# BAAAHS-BRN01-C.net
KiCad netlist of a schematic drawn in EAGLE
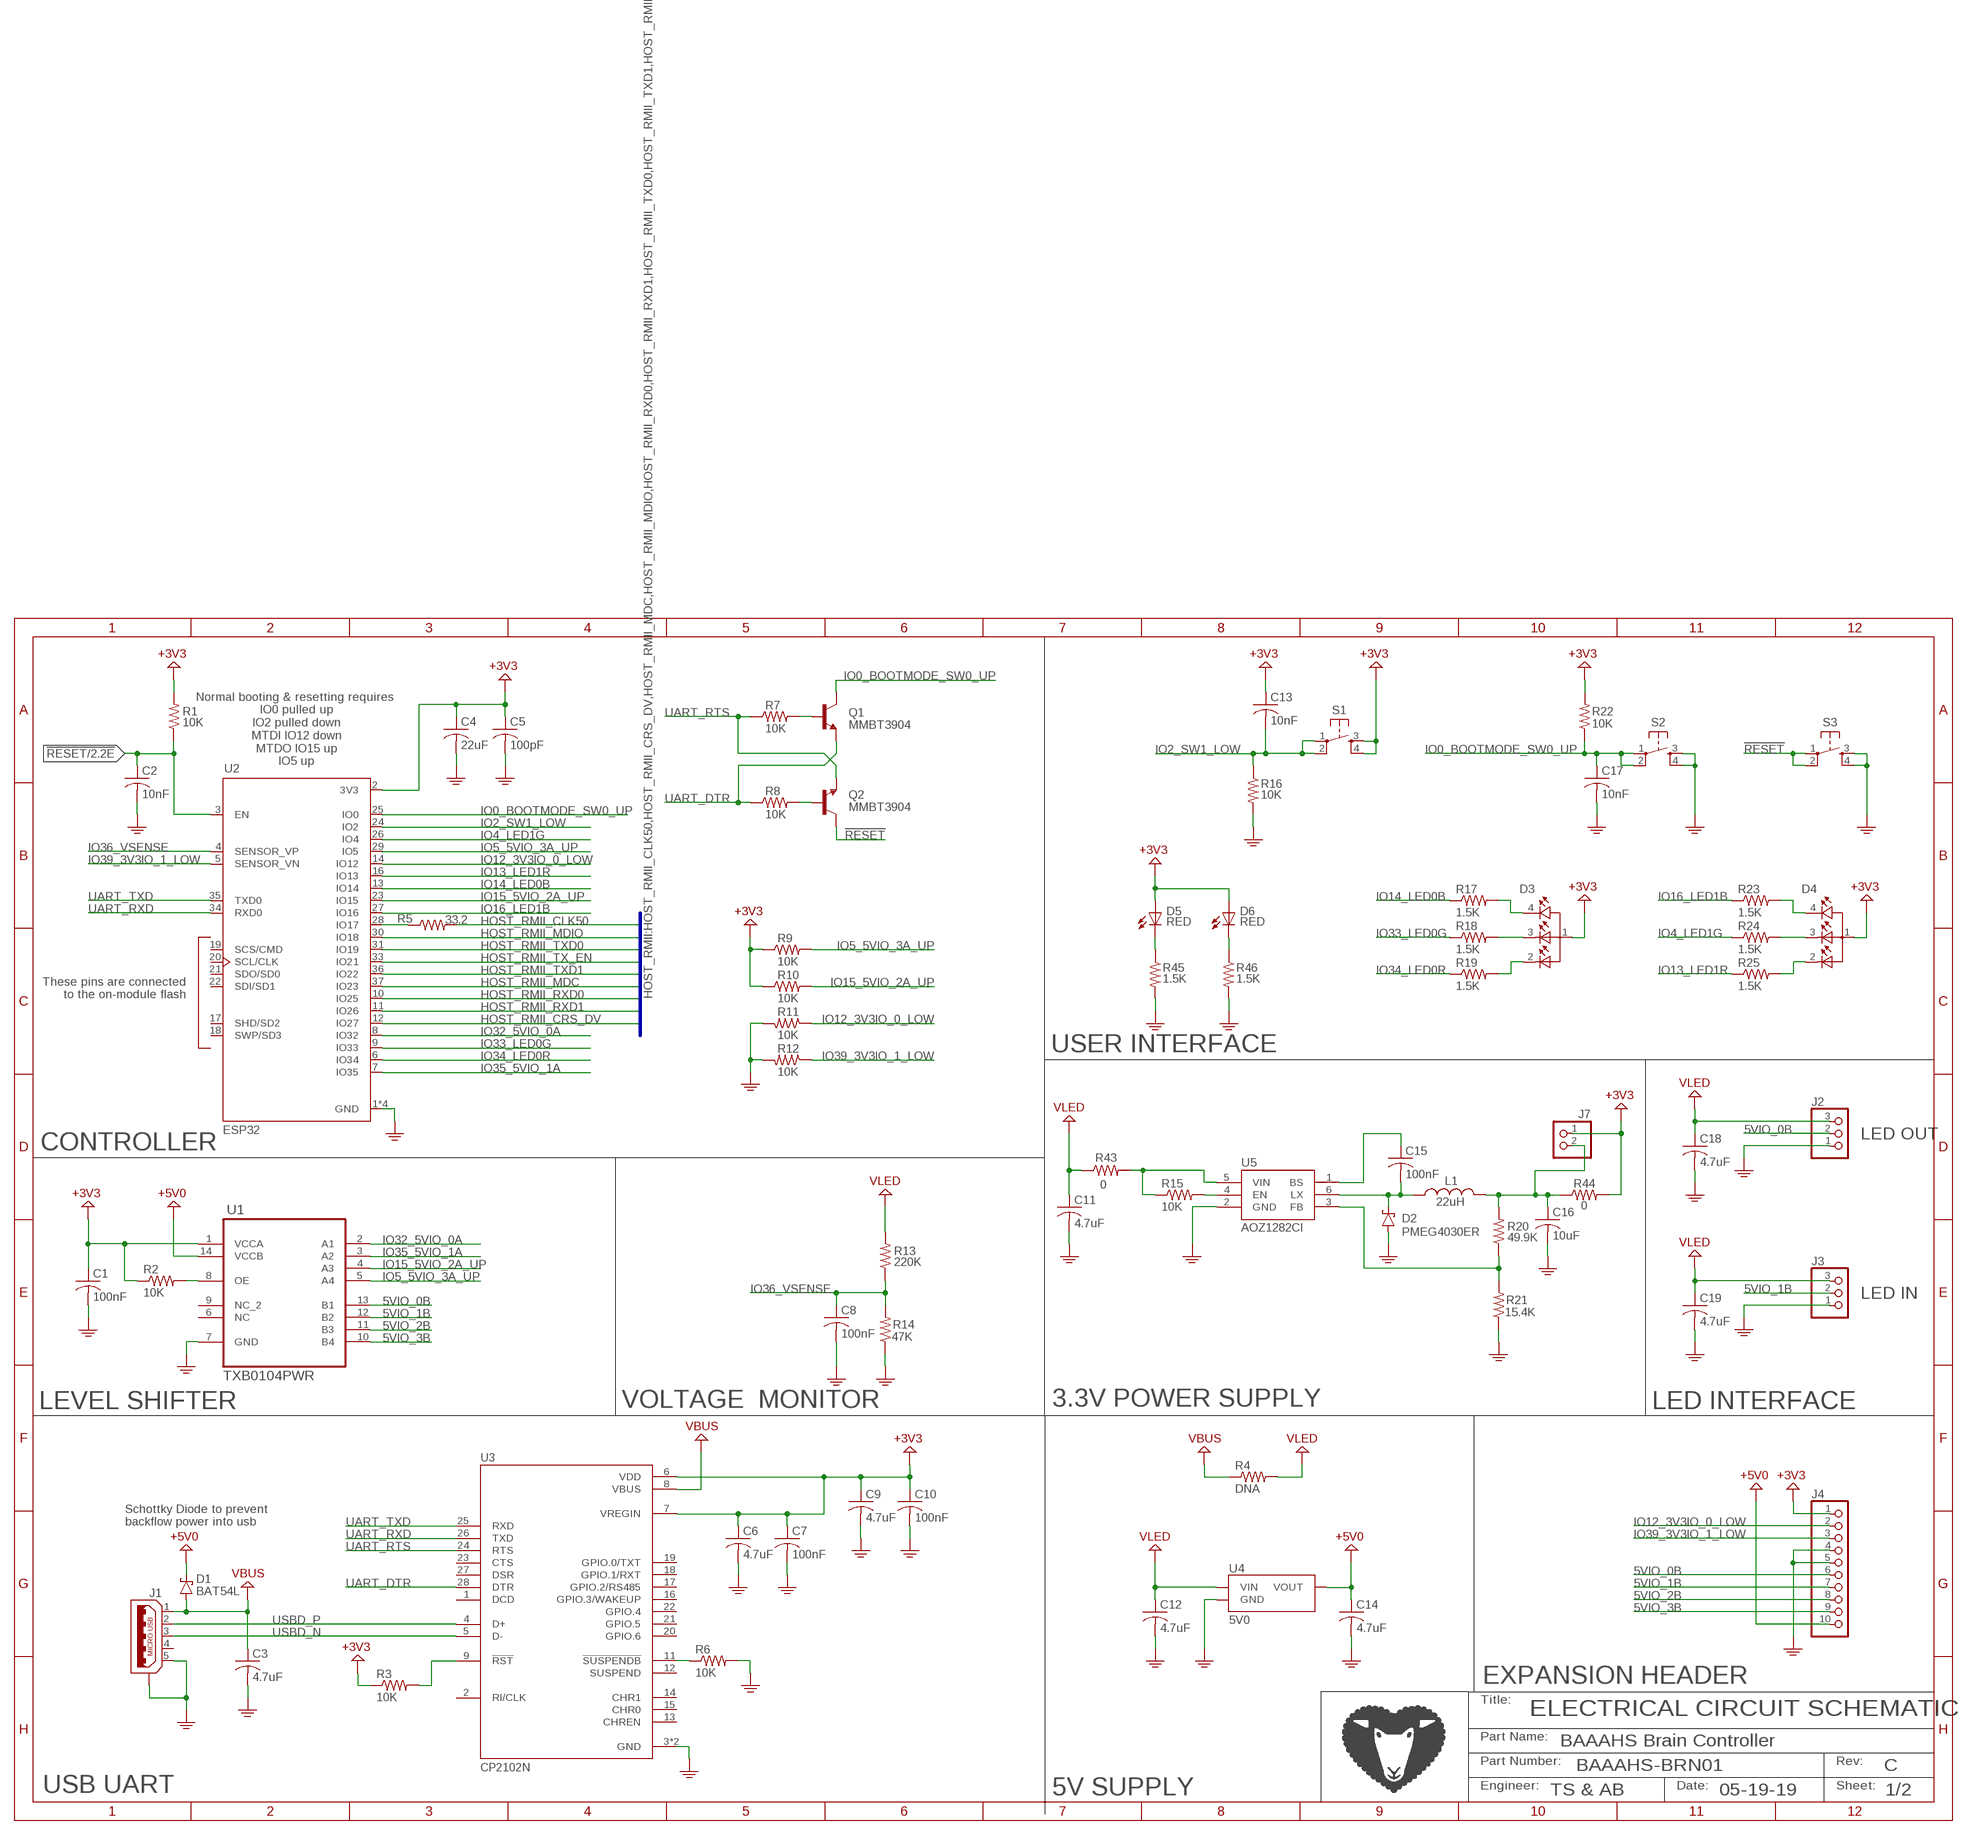
[diagram p0: schematic, sheet 1]
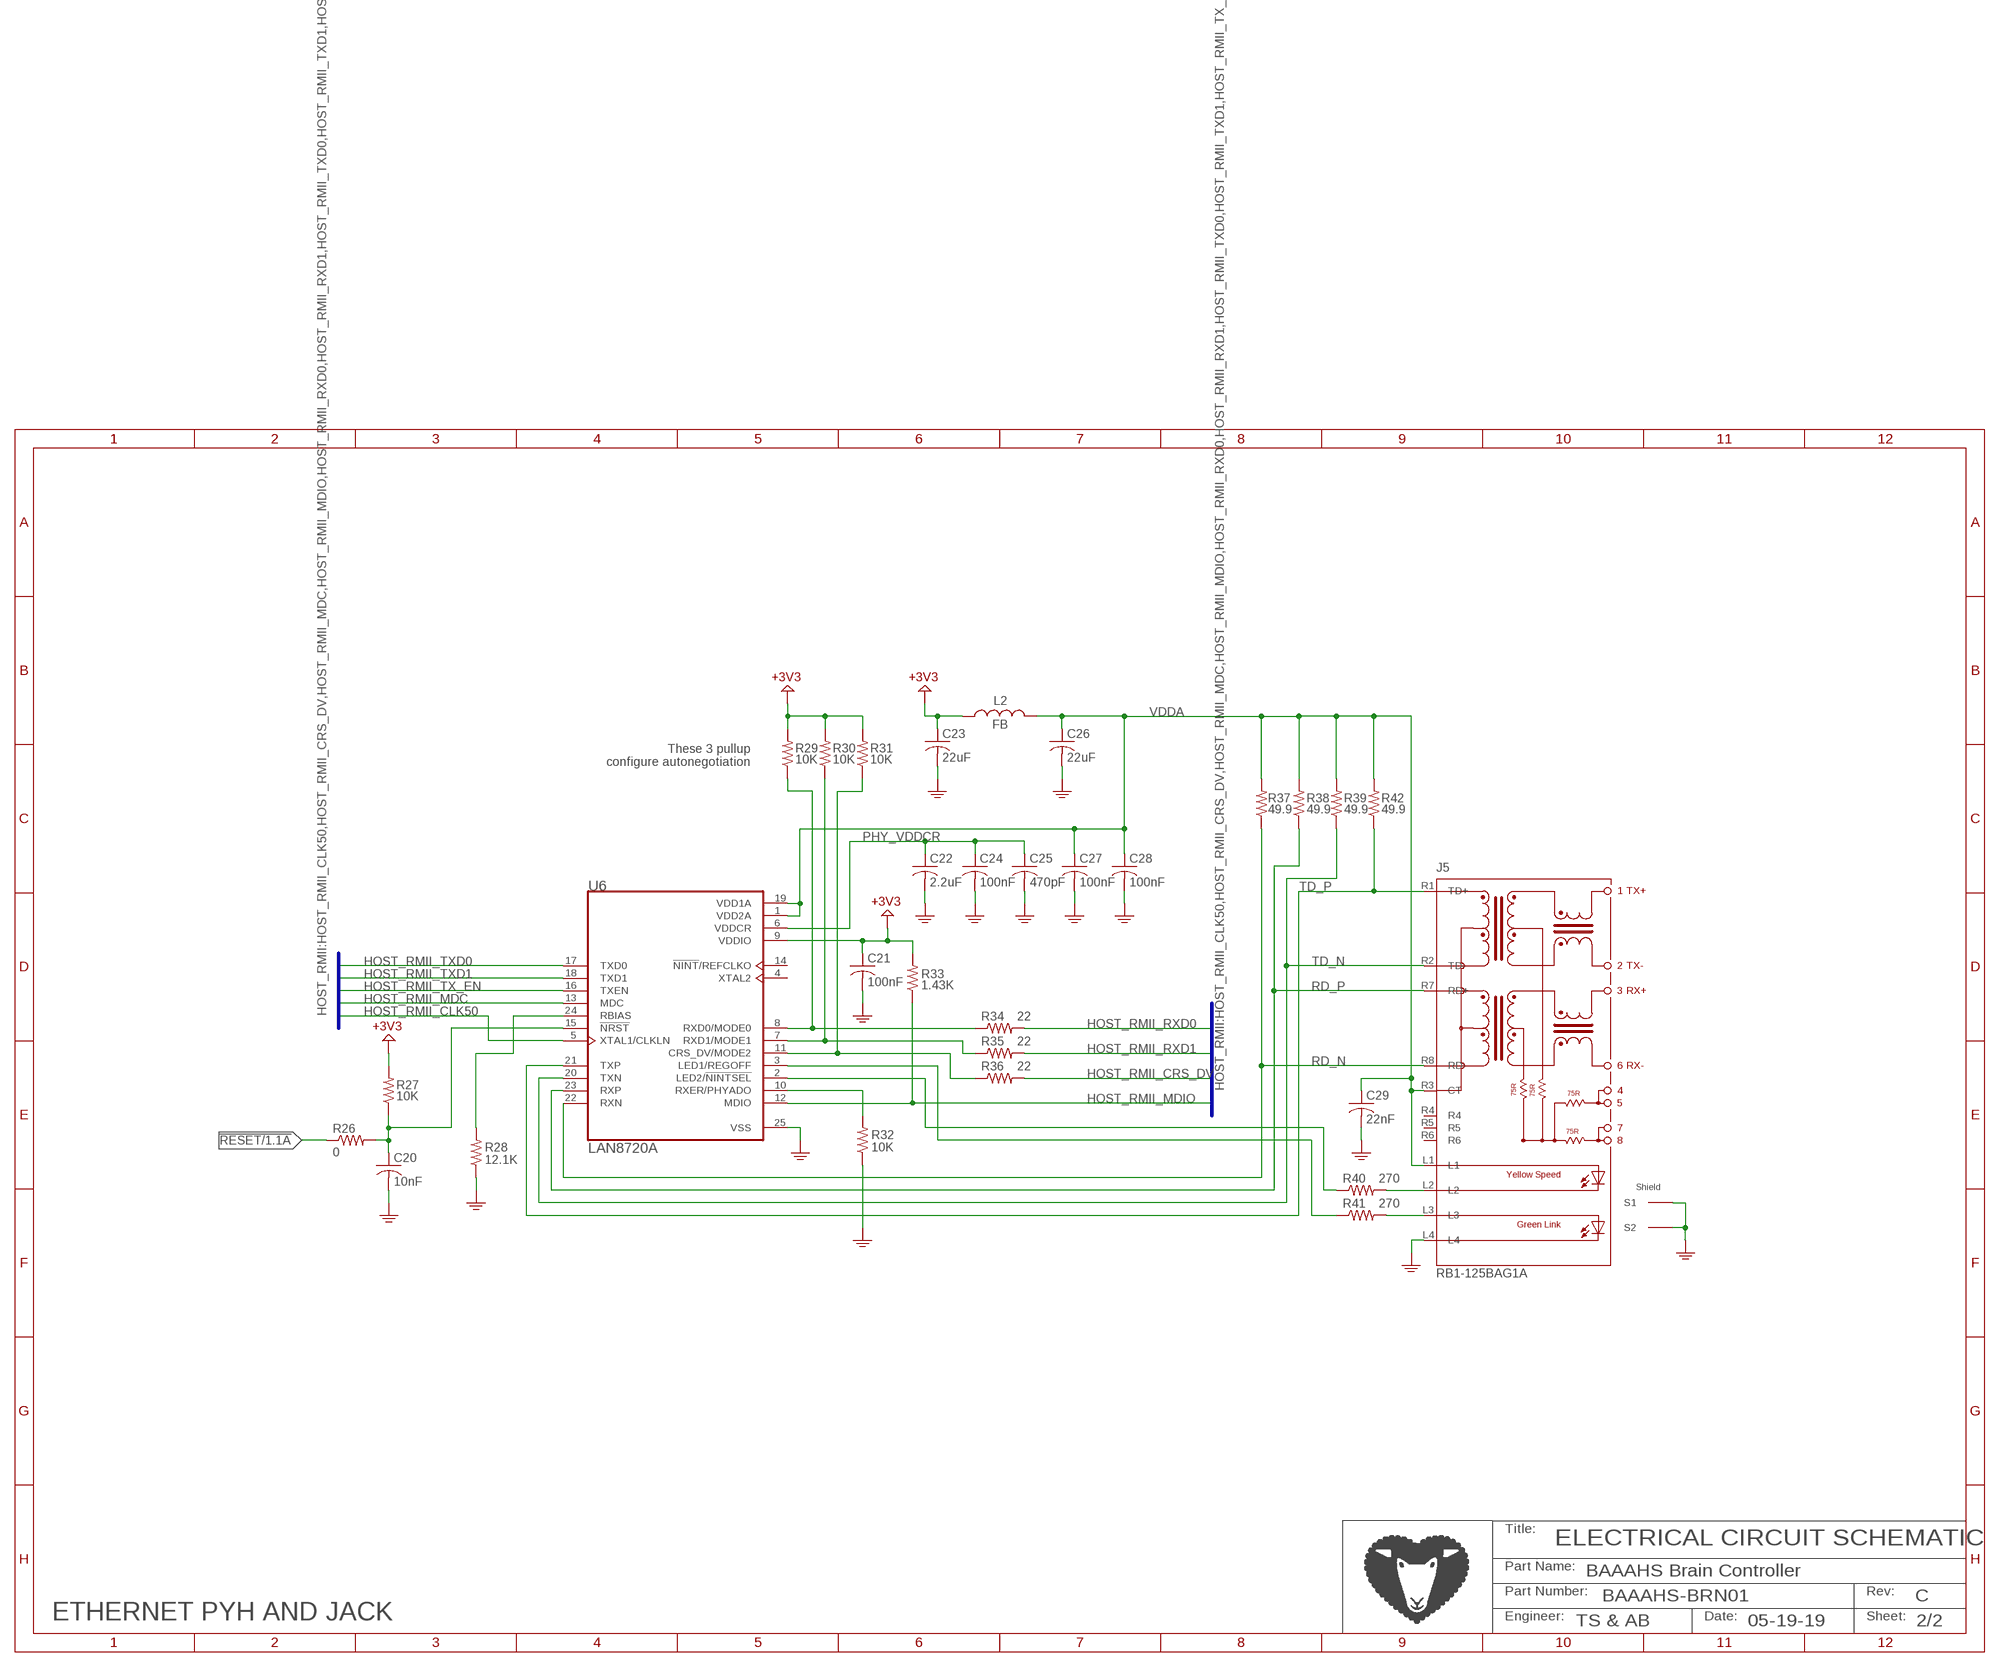
[diagram p1: schematic, sheet 2]

(export (version "E")
  (design (tool "Eeschema 10.0.6"))
  (components
    (comp (ref "C20")
      (value "10nF")
      (footprint "eagle-import:C0402")
      (fields (field (name "TOLERANCE") "+/-10%") (field (name "VOLTAGE") "16V"))
      (libsource (lib "eagle-import") (part "C-C0402-10NF_16V_10%"))
    )
    (comp (ref "C21")
      (value "100nF")
      (footprint "eagle-import:C0402")
      (fields (field (name "TOLERANCE") "+/-10%") (field (name "VOLTAGE") "25V"))
      (libsource (lib "eagle-import") (part "C-C0402-100NF_25V_10%"))
    )
    (comp (ref "C22")
      (value "2.2uF")
      (footprint "eagle-import:C0603")
      (fields (field (name "TOLERANCE") "+/-10%") (field (name "VOLTAGE") "16V"))
      (libsource (lib "eagle-import") (part "C-C0603-2.2UF_16V_10%"))
    )
    (comp (ref "C23")
      (value "22uF")
      (footprint "eagle-import:C0603")
      (fields (field (name "TOLERANCE") "+/-20%") (field (name "VOLTAGE") "10V"))
      (libsource (lib "eagle-import") (part "C-C0603-22UF_10V_20%"))
    )
    (comp (ref "C24")
      (value "100nF")
      (footprint "eagle-import:C0402")
      (fields (field (name "TOLERANCE") "+/-10%") (field (name "VOLTAGE") "25V"))
      (libsource (lib "eagle-import") (part "C-C0402-100NF_25V_10%"))
    )
    (comp (ref "C25")
      (value "470pF")
      (footprint "eagle-import:C0402")
      (fields (field (name "TOLERANCE") "+/-10%") (field (name "VOLTAGE") "50V"))
      (libsource (lib "eagle-import") (part "C-C0402-470PF_50V_10%"))
    )
    (comp (ref "C26")
      (value "22uF")
      (footprint "eagle-import:C0603")
      (fields (field (name "TOLERANCE") "+/-20%") (field (name "VOLTAGE") "10V"))
      (libsource (lib "eagle-import") (part "C-C0603-22UF_10V_20%"))
    )
    (comp (ref "C27")
      (value "100nF")
      (footprint "eagle-import:C0402")
      (fields (field (name "TOLERANCE") "+/-10%") (field (name "VOLTAGE") "25V"))
      (libsource (lib "eagle-import") (part "C-C0402-100NF_25V_10%"))
    )
    (comp (ref "C28")
      (value "100nF")
      (footprint "eagle-import:C0402")
      (fields (field (name "TOLERANCE") "+/-10%") (field (name "VOLTAGE") "25V"))
      (libsource (lib "eagle-import") (part "C-C0402-100NF_25V_10%"))
    )
    (comp (ref "C29")
      (value "22nF")
      (footprint "eagle-import:C0402")
      (fields (field (name "TOLERANCE") "+/-10%") (field (name "VOLTAGE") "16V"))
      (libsource (lib "eagle-import") (part "C-C0402-22NF_16V_10%"))
    )
    (comp (ref "J5")
      (value "RB1-125BAG1A")
      (footprint "eagle-import:WIZNET_RB1-125BAG1A")
      (libsource (lib "eagle-import") (part "RB1-125BAG1A"))
    )
    (comp (ref "L2")
      (value "FB")
      (footprint "eagle-import:L0603")
      (libsource (lib "eagle-import") (part "FB-L0603-600OHM_0.2A"))
    )
    (comp (ref "R26")
      (value "0")
      (footprint "eagle-import:R0402")
      (fields (field (name "POWER") "1/16W") (field (name "TOLERANCE") "1%"))
      (libsource (lib "eagle-import") (part "R-R0402-0_1%"))
    )
    (comp (ref "R27")
      (value "10K")
      (footprint "eagle-import:R0402")
      (fields (field (name "POWER") "1/16W") (field (name "TOLERANCE") "1%"))
      (libsource (lib "eagle-import") (part "R-R0402-10K_1%"))
    )
    (comp (ref "R28")
      (value "12.1K")
      (footprint "eagle-import:R0402")
      (fields (field (name "POWER") "1/16W") (field (name "TOLERANCE") "1%"))
      (libsource (lib "eagle-import") (part "R-R0402-12.1K_1%"))
    )
    (comp (ref "R29")
      (value "10K")
      (footprint "eagle-import:R0402")
      (fields (field (name "POWER") "1/16W") (field (name "TOLERANCE") "1%"))
      (libsource (lib "eagle-import") (part "R-R0402-10K_1%"))
    )
    (comp (ref "R30")
      (value "10K")
      (footprint "eagle-import:R0402")
      (fields (field (name "POWER") "1/16W") (field (name "TOLERANCE") "1%"))
      (libsource (lib "eagle-import") (part "R-R0402-10K_1%"))
    )
    (comp (ref "R31")
      (value "10K")
      (footprint "eagle-import:R0402")
      (fields (field (name "POWER") "1/16W") (field (name "TOLERANCE") "1%"))
      (libsource (lib "eagle-import") (part "R-R0402-10K_1%"))
    )
    (comp (ref "R32")
      (value "10K")
      (footprint "eagle-import:R0402")
      (fields (field (name "POWER") "1/16W") (field (name "TOLERANCE") "1%"))
      (libsource (lib "eagle-import") (part "R-R0402-10K_1%"))
    )
    (comp (ref "R33")
      (value "1.43K")
      (footprint "eagle-import:R0402")
      (fields (field (name "POWER") "1/16W") (field (name "TOLERANCE") "1%"))
      (libsource (lib "eagle-import") (part "R-R0402-1.43K_1%"))
    )
    (comp (ref "R34")
      (value "22")
      (footprint "eagle-import:R0402")
      (fields (field (name "POWER") "1/16W") (field (name "TOLERANCE") "1%"))
      (libsource (lib "eagle-import") (part "R-R0402-22_1%"))
    )
    (comp (ref "R35")
      (value "22")
      (footprint "eagle-import:R0402")
      (fields (field (name "POWER") "1/16W") (field (name "TOLERANCE") "1%"))
      (libsource (lib "eagle-import") (part "R-R0402-22_1%"))
    )
    (comp (ref "R36")
      (value "22")
      (footprint "eagle-import:R0402")
      (fields (field (name "POWER") "1/16W") (field (name "TOLERANCE") "1%"))
      (libsource (lib "eagle-import") (part "R-R0402-22_1%"))
    )
    (comp (ref "R37")
      (value "49.9")
      (footprint "eagle-import:R0402")
      (fields (field (name "POWER") "1/16W") (field (name "TOLERANCE") "1%"))
      (libsource (lib "eagle-import") (part "R-R0402-49.9_1%"))
    )
    (comp (ref "R38")
      (value "49.9")
      (footprint "eagle-import:R0402")
      (fields (field (name "POWER") "1/16W") (field (name "TOLERANCE") "1%"))
      (libsource (lib "eagle-import") (part "R-R0402-49.9_1%"))
    )
    (comp (ref "R39")
      (value "49.9")
      (footprint "eagle-import:R0402")
      (fields (field (name "POWER") "1/16W") (field (name "TOLERANCE") "1%"))
      (libsource (lib "eagle-import") (part "R-R0402-49.9_1%"))
    )
    (comp (ref "R40")
      (value "270")
      (footprint "eagle-import:R0402")
      (fields (field (name "POWER") "1/16W") (field (name "TOLERANCE") "1%"))
      (libsource (lib "eagle-import") (part "R-R0402-270_1%"))
    )
    (comp (ref "R41")
      (value "270")
      (footprint "eagle-import:R0402")
      (fields (field (name "POWER") "1/16W") (field (name "TOLERANCE") "1%"))
      (libsource (lib "eagle-import") (part "R-R0402-270_1%"))
    )
    (comp (ref "R42")
      (value "49.9")
      (footprint "eagle-import:R0402")
      (fields (field (name "POWER") "1/16W") (field (name "TOLERANCE") "1%"))
      (libsource (lib "eagle-import") (part "R-R0402-49.9_1%"))
    )
    (comp (ref "U6")
      (value "LAN8720A")
      (footprint "eagle-import:QFN50P400X400X100-25N")
      (libsource (lib "eagle-import") (part "LAN8720A-CP"))
    )
    (comp (ref "C1")
      (value "100nF")
      (footprint "eagle-import:C0402")
      (fields (field (name "TOLERANCE") "+/-10%") (field (name "VOLTAGE") "25V"))
      (libsource (lib "eagle-import") (part "C-C0402-100NF_25V_10%"))
    )
    (comp (ref "C2")
      (value "10nF")
      (footprint "eagle-import:C0402")
      (fields (field (name "TOLERANCE") "+/-10%") (field (name "VOLTAGE") "16V"))
      (libsource (lib "eagle-import") (part "C-C0402-10NF_16V_10%"))
    )
    (comp (ref "C3")
      (value "4.7uF")
      (footprint "eagle-import:C0402")
      (fields (field (name "TOLERANCE") "+/-10%") (field (name "VOLTAGE") "10V"))
      (libsource (lib "eagle-import") (part "C-C0402-4.7UF_10V_10%"))
    )
    (comp (ref "C4")
      (value "22uF")
      (footprint "eagle-import:C0603")
      (fields (field (name "TOLERANCE") "+/-20%") (field (name "VOLTAGE") "10V"))
      (libsource (lib "eagle-import") (part "C-C0603-22UF_10V_20%"))
    )
    (comp (ref "C5")
      (value "100pF")
      (footprint "eagle-import:C0402")
      (fields (field (name "TOLERANCE") "+/-5%") (field (name "VOLTAGE") "50V"))
      (libsource (lib "eagle-import") (part "C-C0402-100PF_50V_5%"))
    )
    (comp (ref "C6")
      (value "4.7uF")
      (footprint "eagle-import:C0402")
      (fields (field (name "TOLERANCE") "+/-10%") (field (name "VOLTAGE") "10V"))
      (libsource (lib "eagle-import") (part "C-C0402-4.7UF_10V_10%"))
    )
    (comp (ref "C7")
      (value "100nF")
      (footprint "eagle-import:C0402")
      (fields (field (name "TOLERANCE") "+/-10%") (field (name "VOLTAGE") "25V"))
      (libsource (lib "eagle-import") (part "C-C0402-100NF_25V_10%"))
    )
    (comp (ref "C8")
      (value "100nF")
      (footprint "eagle-import:C0402")
      (fields (field (name "TOLERANCE") "+/-10%") (field (name "VOLTAGE") "25V"))
      (libsource (lib "eagle-import") (part "C-C0402-100NF_25V_10%"))
    )
    (comp (ref "C9")
      (value "4.7uF")
      (footprint "eagle-import:C0402")
      (fields (field (name "TOLERANCE") "+/-10%") (field (name "VOLTAGE") "10V"))
      (libsource (lib "eagle-import") (part "C-C0402-4.7UF_10V_10%"))
    )
    (comp (ref "C10")
      (value "100nF")
      (footprint "eagle-import:C0402")
      (fields (field (name "TOLERANCE") "+/-10%") (field (name "VOLTAGE") "25V"))
      (libsource (lib "eagle-import") (part "C-C0402-100NF_25V_10%"))
    )
    (comp (ref "C11")
      (value "4.7uF")
      (footprint "eagle-import:C0603")
      (fields (field (name "TOLERANCE") "+/-10%") (field (name "VOLTAGE") "25V"))
      (libsource (lib "eagle-import") (part "C-C0603-4.7UF_25V_10%"))
    )
    (comp (ref "C12")
      (value "4.7uF")
      (footprint "eagle-import:C0603")
      (fields (field (name "TOLERANCE") "+/-10%") (field (name "VOLTAGE") "25V"))
      (libsource (lib "eagle-import") (part "C-C0603-4.7UF_25V_10%"))
    )
    (comp (ref "C13")
      (value "10nF")
      (footprint "eagle-import:C0402")
      (fields (field (name "TOLERANCE") "+/-10%") (field (name "VOLTAGE") "16V"))
      (libsource (lib "eagle-import") (part "C-C0402-10NF_16V_10%"))
    )
    (comp (ref "C14")
      (value "4.7uF")
      (footprint "eagle-import:C0402")
      (fields (field (name "TOLERANCE") "+/-10%") (field (name "VOLTAGE") "10V"))
      (libsource (lib "eagle-import") (part "C-C0402-4.7UF_10V_10%"))
    )
    (comp (ref "C15")
      (value "100nF")
      (footprint "eagle-import:C0402")
      (fields (field (name "TOLERANCE") "+/-10%") (field (name "VOLTAGE") "25V"))
      (libsource (lib "eagle-import") (part "C-C0402-100NF_25V_10%"))
    )
    (comp (ref "C16")
      (value "10uF")
      (footprint "eagle-import:C0603")
      (fields (field (name "TOLERANCE") "+/-20%") (field (name "VOLTAGE") "25V"))
      (libsource (lib "eagle-import") (part "C-C0603-10UF_25V_20%"))
    )
    (comp (ref "C17")
      (value "10nF")
      (footprint "eagle-import:C0402")
      (fields (field (name "TOLERANCE") "+/-10%") (field (name "VOLTAGE") "16V"))
      (libsource (lib "eagle-import") (part "C-C0402-10NF_16V_10%"))
    )
    (comp (ref "C18")
      (value "4.7uF")
      (footprint "eagle-import:C0603")
      (fields (field (name "TOLERANCE") "+/-10%") (field (name "VOLTAGE") "25V"))
      (libsource (lib "eagle-import") (part "C-C0603-4.7UF_25V_10%"))
    )
    (comp (ref "C19")
      (value "4.7uF")
      (footprint "eagle-import:C0603")
      (fields (field (name "TOLERANCE") "+/-10%") (field (name "VOLTAGE") "25V"))
      (libsource (lib "eagle-import") (part "C-C0603-4.7UF_25V_10%"))
    )
    (comp (ref "D1")
      (value "BAT54L")
      (footprint "eagle-import:SOT23")
      (libsource (lib "eagle-import") (part "D_SCHOTTKY-SOT23"))
    )
    (comp (ref "D2")
      (value "PMEG4030ER")
      (footprint "eagle-import:SOD123")
      (libsource (lib "eagle-import") (part "D_SCHOTTKY-SOD123-PMEG4030ER_40V"))
    )
    (comp (ref "D3")
      (value "APTF1616LSEEZGKQBKC")
      (footprint "eagle-import:LEDSC160X160X070-4N")
      (libsource (lib "eagle-import") (part "APTF1616LSEEZGKQBKC"))
    )
    (comp (ref "D4")
      (value "APTF1616LSEEZGKQBKC")
      (footprint "eagle-import:LEDSC160X160X070-4N")
      (libsource (lib "eagle-import") (part "APTF1616LSEEZGKQBKC"))
    )
    (comp (ref "D5")
      (value "RED")
      (footprint "eagle-import:D0603")
      (libsource (lib "eagle-import") (part "LED-D0603-RED_54MCD"))
    )
    (comp (ref "D6")
      (value "RED")
      (footprint "eagle-import:D0603")
      (libsource (lib "eagle-import") (part "LED-D0603-RED_54MCD"))
    )
    (comp (ref "J1")
      (value "USB_MICRO-FCI-USB_MICRO_A_RA")
      (footprint "eagle-import:USB_MICRO_A_RA")
      (libsource (lib "eagle-import") (part "USB_MICRO-USB_MICRO_A_RA-FCI"))
    )
    (comp (ref "J2")
      (value "PINHD1X3-20AWG")
      (footprint "eagle-import:3WAY_LED_WIRES")
      (libsource (lib "eagle-import") (part "PINHD1X3-20AWG"))
    )
    (comp (ref "J3")
      (value "PINHD1X3-20AWG")
      (footprint "eagle-import:3WAY_LED_WIRES")
      (libsource (lib "eagle-import") (part "PINHD1X3-20AWG"))
    )
    (comp (ref "J4")
      (value "PINHD1X10-1X10")
      (footprint "eagle-import:1X10")
      (libsource (lib "eagle-import") (part "PINHD1X10-1X10"))
    )
    (comp (ref "J7")
      (value "PINHD1X2-1X02")
      (footprint "eagle-import:1X02")
      (libsource (lib "eagle-import") (part "PINHD1X2-1X02"))
    )
    (comp (ref "L1")
      (value "22uH")
      (footprint "eagle-import:NRG4026")
      (libsource (lib "eagle-import") (part "L-NRG4026-22UH__290MOHM_700MA"))
    )
    (comp (ref "Q1")
      (value "MMBT3904")
      (footprint "eagle-import:SOT23")
      (fields (field (name "VOLTAGE") "40V"))
      (libsource (lib "eagle-import") (part "NPN-SOT23-MMBT3904_40V"))
    )
    (comp (ref "Q2")
      (value "MMBT3904")
      (footprint "eagle-import:SOT23")
      (fields (field (name "VOLTAGE") "40V"))
      (libsource (lib "eagle-import") (part "NPN-SOT23-MMBT3904_40V"))
    )
    (comp (ref "R1")
      (value "10K")
      (footprint "eagle-import:R0402")
      (fields (field (name "POWER") "1/16W") (field (name "TOLERANCE") "1%"))
      (libsource (lib "eagle-import") (part "R-R0402-10K_1%"))
    )
    (comp (ref "R2")
      (value "10K")
      (footprint "eagle-import:R0402")
      (fields (field (name "POWER") "1/16W") (field (name "TOLERANCE") "1%"))
      (libsource (lib "eagle-import") (part "R-R0402-10K_1%"))
    )
    (comp (ref "R3")
      (value "10K")
      (footprint "eagle-import:R0402")
      (fields (field (name "POWER") "1/16W") (field (name "TOLERANCE") "1%"))
      (libsource (lib "eagle-import") (part "R-R0402-10K_1%"))
    )
    (comp (ref "R4")
      (value "DNA")
      (footprint "eagle-import:R0603")
      (fields (field (name "POWER") "1/16W"))
      (libsource (lib "eagle-import") (part "R-R0603-DNA"))
    )
    (comp (ref "R5")
      (value "33.2")
      (footprint "eagle-import:R0402")
      (fields (field (name "POWER") "1/16W") (field (name "TOLERANCE") "1%"))
      (libsource (lib "eagle-import") (part "R-R0402-33.2_1%"))
    )
    (comp (ref "R6")
      (value "10K")
      (footprint "eagle-import:R0402")
      (fields (field (name "POWER") "1/16W") (field (name "TOLERANCE") "1%"))
      (libsource (lib "eagle-import") (part "R-R0402-10K_1%"))
    )
    (comp (ref "R7")
      (value "10K")
      (footprint "eagle-import:R0402")
      (fields (field (name "POWER") "1/16W") (field (name "TOLERANCE") "1%"))
      (libsource (lib "eagle-import") (part "R-R0402-10K_1%"))
    )
    (comp (ref "R8")
      (value "10K")
      (footprint "eagle-import:R0402")
      (fields (field (name "POWER") "1/16W") (field (name "TOLERANCE") "1%"))
      (libsource (lib "eagle-import") (part "R-R0402-10K_1%"))
    )
    (comp (ref "R9")
      (value "10K")
      (footprint "eagle-import:R0402")
      (fields (field (name "POWER") "1/16W") (field (name "TOLERANCE") "1%"))
      (libsource (lib "eagle-import") (part "R-R0402-10K_1%"))
    )
    (comp (ref "R10")
      (value "10K")
      (footprint "eagle-import:R0402")
      (fields (field (name "POWER") "1/16W") (field (name "TOLERANCE") "1%"))
      (libsource (lib "eagle-import") (part "R-R0402-10K_1%"))
    )
    (comp (ref "R11")
      (value "10K")
      (footprint "eagle-import:R0402")
      (fields (field (name "POWER") "1/16W") (field (name "TOLERANCE") "1%"))
      (libsource (lib "eagle-import") (part "R-R0402-10K_1%"))
    )
    (comp (ref "R12")
      (value "10K")
      (footprint "eagle-import:R0402")
      (fields (field (name "POWER") "1/16W") (field (name "TOLERANCE") "1%"))
      (libsource (lib "eagle-import") (part "R-R0402-10K_1%"))
    )
    (comp (ref "R13")
      (value "220K")
      (footprint "eagle-import:R0402")
      (fields (field (name "POWER") "1/16W") (field (name "TOLERANCE") "1%"))
      (libsource (lib "eagle-import") (part "R-R0402-220K_1%"))
    )
    (comp (ref "R14")
      (value "47K")
      (footprint "eagle-import:R0402")
      (fields (field (name "POWER") "1/16W") (field (name "TOLERANCE") "1%"))
      (libsource (lib "eagle-import") (part "R-R0402-47K_1%"))
    )
    (comp (ref "R15")
      (value "10K")
      (footprint "eagle-import:R0402")
      (fields (field (name "POWER") "1/16W") (field (name "TOLERANCE") "1%"))
      (libsource (lib "eagle-import") (part "R-R0402-10K_1%"))
    )
    (comp (ref "R16")
      (value "10K")
      (footprint "eagle-import:R0402")
      (fields (field (name "POWER") "1/16W") (field (name "TOLERANCE") "1%"))
      (libsource (lib "eagle-import") (part "R-R0402-10K_1%"))
    )
    (comp (ref "R17")
      (value "1.5K")
      (footprint "eagle-import:R0402")
      (fields (field (name "POWER") "1/16W") (field (name "TOLERANCE") "1%"))
      (libsource (lib "eagle-import") (part "R-R0402-1.5K_1%"))
    )
    (comp (ref "R18")
      (value "1.5K")
      (footprint "eagle-import:R0402")
      (fields (field (name "POWER") "1/16W") (field (name "TOLERANCE") "1%"))
      (libsource (lib "eagle-import") (part "R-R0402-1.5K_1%"))
    )
    (comp (ref "R19")
      (value "1.5K")
      (footprint "eagle-import:R0402")
      (fields (field (name "POWER") "1/16W") (field (name "TOLERANCE") "1%"))
      (libsource (lib "eagle-import") (part "R-R0402-1.5K_1%"))
    )
    (comp (ref "R20")
      (value "49.9K")
      (footprint "eagle-import:R0402")
      (fields (field (name "POWER") "1/16W") (field (name "TOLERANCE") "1%"))
      (libsource (lib "eagle-import") (part "R-R0402-49.9K_1%"))
    )
    (comp (ref "R21")
      (value "15.4K")
      (footprint "eagle-import:R0402")
      (fields (field (name "POWER") "1/16W") (field (name "TOLERANCE") "1%"))
      (libsource (lib "eagle-import") (part "R-R0402-15.4K_1%"))
    )
    (comp (ref "R22")
      (value "10K")
      (footprint "eagle-import:R0402")
      (fields (field (name "POWER") "1/16W") (field (name "TOLERANCE") "1%"))
      (libsource (lib "eagle-import") (part "R-R0402-10K_1%"))
    )
    (comp (ref "R23")
      (value "1.5K")
      (footprint "eagle-import:R0402")
      (fields (field (name "POWER") "1/16W") (field (name "TOLERANCE") "1%"))
      (libsource (lib "eagle-import") (part "R-R0402-1.5K_1%"))
    )
    (comp (ref "R24")
      (value "1.5K")
      (footprint "eagle-import:R0402")
      (fields (field (name "POWER") "1/16W") (field (name "TOLERANCE") "1%"))
      (libsource (lib "eagle-import") (part "R-R0402-1.5K_1%"))
    )
    (comp (ref "R25")
      (value "1.5K")
      (footprint "eagle-import:R0402")
      (fields (field (name "POWER") "1/16W") (field (name "TOLERANCE") "1%"))
      (libsource (lib "eagle-import") (part "R-R0402-1.5K_1%"))
    )
    (comp (ref "R43")
      (value "0")
      (footprint "eagle-import:R0603")
      (fields (field (name "POWER") "1/10W") (field (name "TOLERANCE") "1%"))
      (libsource (lib "eagle-import") (part "R-R0603-0_1%"))
    )
    (comp (ref "R44")
      (value "0")
      (footprint "eagle-import:R0603")
      (fields (field (name "POWER") "1/10W") (field (name "TOLERANCE") "1%"))
      (libsource (lib "eagle-import") (part "R-R0603-0_1%"))
    )
    (comp (ref "R45")
      (value "1.5K")
      (footprint "eagle-import:R0402")
      (fields (field (name "POWER") "1/16W") (field (name "TOLERANCE") "1%"))
      (libsource (lib "eagle-import") (part "R-R0402-1.5K_1%"))
    )
    (comp (ref "R46")
      (value "1.5K")
      (footprint "eagle-import:R0402")
      (fields (field (name "POWER") "1/16W") (field (name "TOLERANCE") "1%"))
      (libsource (lib "eagle-import") (part "R-R0402-1.5K_1%"))
    )
    (comp (ref "S1")
      (value "SW4-SM6MM")
      (footprint "eagle-import:SM6MM")
      (libsource (lib "eagle-import") (part "SW4-SM6MM"))
    )
    (comp (ref "S2")
      (value "SW4-SM6MM")
      (footprint "eagle-import:SM6MM")
      (libsource (lib "eagle-import") (part "SW4-SM6MM"))
    )
    (comp (ref "S3")
      (value "SW4-SM6MM")
      (footprint "eagle-import:SM6MM")
      (libsource (lib "eagle-import") (part "SW4-SM6MM"))
    )
    (comp (ref "U1")
      (value "TXB0104PWR")
      (footprint "eagle-import:SOP65P640X120-14N")
      (libsource (lib "eagle-import") (part "TXB0104PWR"))
    )
    (comp (ref "U2")
      (value "ESP32")
      (footprint "eagle-import:MODULE_ESP32WROOM32D")
      (libsource (lib "eagle-import") (part "ESP32WROOM32D-MODULE_ESP32WROOM32D"))
    )
    (comp (ref "U3")
      (value "CP2102N")
      (footprint "eagle-import:QFN50P500X500X80_29N")
      (libsource (lib "eagle-import") (part "CP2102N-A01-GQFN28"))
    )
    (comp (ref "U4")
      (value "5V0")
      (footprint "eagle-import:SOT23")
      (libsource (lib "eagle-import") (part "TLV76050DBZR-SOT23"))
    )
    (comp (ref "U5")
      (value "AOZ1282CI")
      (footprint "eagle-import:SOT23_6")
      (libsource (lib "eagle-import") (part "AOZ1282CI-SOT23_6"))
    )
  )
  (nets
    (net (code "5") (name "3V3") (class "Default")
      (node (ref "C1") (pin "1") (pinfunction "1_1") (pintype "passive"))
      (node (ref "C10") (pin "1") (pinfunction "1_1") (pintype "passive"))
      (node (ref "C13") (pin "1") (pinfunction "1_1") (pintype "passive"))
      (node (ref "C21") (pin "1") (pinfunction "1_1") (pintype "passive"))
      (node (ref "C23") (pin "1") (pinfunction "1_1") (pintype "passive"))
      (node (ref "C4") (pin "1") (pinfunction "1_1") (pintype "passive"))
      (node (ref "C5") (pin "1") (pinfunction "1_1") (pintype "passive"))
      (node (ref "C6") (pin "1") (pinfunction "1_1") (pintype "passive"))
      (node (ref "C7") (pin "1") (pinfunction "1_1") (pintype "passive"))
      (node (ref "C9") (pin "1") (pinfunction "1_1") (pintype "passive"))
      (node (ref "D3") (pin "1") (pinfunction "1_1") (pintype "passive"))
      (node (ref "D4") (pin "1") (pinfunction "1_1") (pintype "passive"))
      (node (ref "D5") (pin "A") (pinfunction "A_A") (pintype "passive"))
      (node (ref "D6") (pin "A") (pinfunction "A_A") (pintype "passive"))
      (node (ref "J4") (pin "1") (pinfunction "1_1") (pintype "passive"))
      (node (ref "J7") (pin "1") (pinfunction "1_1") (pintype "passive"))
      (node (ref "L2") (pin "1") (pinfunction "1_1") (pintype "passive"))
      (node (ref "R1") (pin "2") (pinfunction "2_2") (pintype "passive"))
      (node (ref "R10") (pin "1") (pinfunction "1_1") (pintype "passive"))
      (node (ref "R2") (pin "1") (pinfunction "1_1") (pintype "passive"))
      (node (ref "R22") (pin "2") (pinfunction "2_2") (pintype "passive"))
      (node (ref "R27") (pin "2") (pinfunction "2_2") (pintype "passive"))
      (node (ref "R29") (pin "2") (pinfunction "2_2") (pintype "passive"))
      (node (ref "R3") (pin "1") (pinfunction "1_1") (pintype "passive"))
      (node (ref "R30") (pin "2") (pinfunction "2_2") (pintype "passive"))
      (node (ref "R31") (pin "2") (pinfunction "2_2") (pintype "passive"))
      (node (ref "R33") (pin "2") (pinfunction "2_2") (pintype "passive"))
      (node (ref "R44") (pin "2") (pinfunction "2_2") (pintype "passive"))
      (node (ref "R9") (pin "1") (pinfunction "1_1") (pintype "passive"))
      (node (ref "S1") (pin "3") (pinfunction "S_3") (pintype "passive"))
      (node (ref "S1") (pin "4") (pinfunction "S1_4") (pintype "passive"))
      (node (ref "U1") (pin "1") (pinfunction "VCCA_1") (pintype "power_in"))
      (node (ref "U2") (pin "2") (pinfunction "3V3_2") (pintype "power_in"))
      (node (ref "U3") (pin "6") (pinfunction "VDD_6") (pintype "power_in"))
      (node (ref "U3") (pin "7") (pinfunction "VREGIN_7") (pintype "power_in"))
      (node (ref "U6") (pin "9") (pinfunction "VDDIO_9") (pintype "power_in"))
    )
    (net (code "6") (name "5V0") (class "Default")
      (node (ref "C14") (pin "1") (pinfunction "1_1") (pintype "passive"))
      (node (ref "D1") (pin "3") (pinfunction "C_3") (pintype "passive"))
      (node (ref "J4") (pin "10") (pinfunction "10_10") (pintype "passive"))
      (node (ref "U1") (pin "14") (pinfunction "VCCB_14") (pintype "power_in"))
      (node (ref "U4") (pin "1") (pinfunction "VOUT_1") (pintype "bidirectional"))
    )
    (net (code "7") (name "5VIO_0B") (class "Default")
      (node (ref "J2") (pin "2") (pinfunction "2_2") (pintype "passive"))
      (node (ref "J4") (pin "6") (pinfunction "6_6") (pintype "passive"))
      (node (ref "U1") (pin "13") (pinfunction "B1_13") (pintype "bidirectional"))
    )
    (net (code "8") (name "5VIO_1B") (class "Default")
      (node (ref "J3") (pin "2") (pinfunction "2_2") (pintype "passive"))
      (node (ref "J4") (pin "7") (pinfunction "7_7") (pintype "passive"))
      (node (ref "U1") (pin "12") (pinfunction "B2_12") (pintype "bidirectional"))
    )
    (net (code "9") (name "5VIO_2B") (class "Default")
      (node (ref "J4") (pin "8") (pinfunction "8_8") (pintype "passive"))
      (node (ref "U1") (pin "11") (pinfunction "B3_11") (pintype "bidirectional"))
    )
    (net (code "10") (name "5VIO_3B") (class "Default")
      (node (ref "J4") (pin "9") (pinfunction "9_9") (pintype "passive"))
      (node (ref "U1") (pin "10") (pinfunction "B4_10") (pintype "bidirectional"))
    )
    (net (code "11") (name "GND") (class "Default")
      (node (ref "C1") (pin "2") (pinfunction "2_2") (pintype "passive"))
      (node (ref "C10") (pin "2") (pinfunction "2_2") (pintype "passive"))
      (node (ref "C11") (pin "2") (pinfunction "2_2") (pintype "passive"))
      (node (ref "C12") (pin "2") (pinfunction "2_2") (pintype "passive"))
      (node (ref "C14") (pin "2") (pinfunction "2_2") (pintype "passive"))
      (node (ref "C16") (pin "2") (pinfunction "2_2") (pintype "passive"))
      (node (ref "C17") (pin "2") (pinfunction "2_2") (pintype "passive"))
      (node (ref "C18") (pin "2") (pinfunction "2_2") (pintype "passive"))
      (node (ref "C19") (pin "2") (pinfunction "2_2") (pintype "passive"))
      (node (ref "C2") (pin "2") (pinfunction "2_2") (pintype "passive"))
      (node (ref "C20") (pin "2") (pinfunction "2_2") (pintype "passive"))
      (node (ref "C21") (pin "2") (pinfunction "2_2") (pintype "passive"))
      (node (ref "C22") (pin "2") (pinfunction "2_2") (pintype "passive"))
      (node (ref "C23") (pin "2") (pinfunction "2_2") (pintype "passive"))
      (node (ref "C24") (pin "2") (pinfunction "2_2") (pintype "passive"))
      (node (ref "C25") (pin "2") (pinfunction "2_2") (pintype "passive"))
      (node (ref "C26") (pin "2") (pinfunction "2_2") (pintype "passive"))
      (node (ref "C27") (pin "2") (pinfunction "2_2") (pintype "passive"))
      (node (ref "C28") (pin "2") (pinfunction "2_2") (pintype "passive"))
      (node (ref "C29") (pin "2") (pinfunction "2_2") (pintype "passive"))
      (node (ref "C3") (pin "2") (pinfunction "2_2") (pintype "passive"))
      (node (ref "C4") (pin "2") (pinfunction "2_2") (pintype "passive"))
      (node (ref "C5") (pin "2") (pinfunction "2_2") (pintype "passive"))
      (node (ref "C6") (pin "2") (pinfunction "2_2") (pintype "passive"))
      (node (ref "C7") (pin "2") (pinfunction "2_2") (pintype "passive"))
      (node (ref "C8") (pin "2") (pinfunction "2_2") (pintype "passive"))
      (node (ref "C9") (pin "2") (pinfunction "2_2") (pintype "passive"))
      (node (ref "D2") (pin "A") (pinfunction "A_A") (pintype "passive"))
      (node (ref "J1") (pin "5") (pinfunction "5_5") (pintype "passive"))
      (node (ref "J1") (pin "S1") (pinfunction "S1_S1") (pintype "bidirectional"))
      (node (ref "J1") (pin "S2") (pinfunction "S1_S2") (pintype "bidirectional"))
      (node (ref "J1") (pin "S3") (pinfunction "S1_S3") (pintype "bidirectional"))
      (node (ref "J1") (pin "S4") (pinfunction "S1_S4") (pintype "bidirectional"))
      (node (ref "J1") (pin "S5") (pinfunction "S1_S5") (pintype "bidirectional"))
      (node (ref "J1") (pin "S6") (pinfunction "S1_S6") (pintype "bidirectional"))
      (node (ref "J2") (pin "1") (pinfunction "3_1") (pintype "passive"))
      (node (ref "J3") (pin "1") (pinfunction "3_1") (pintype "passive"))
      (node (ref "J4") (pin "4") (pinfunction "4_4") (pintype "passive"))
      (node (ref "J4") (pin "5") (pinfunction "5_5") (pintype "passive"))
      (node (ref "J5") (pin "L4") (pinfunction "L4_L4") (pintype "passive"))
      (node (ref "J5") (pin "S1") (pinfunction "S1_S1") (pintype "power_in"))
      (node (ref "J5") (pin "S2") (pinfunction "S2_S2") (pintype "power_in"))
      (node (ref "R11") (pin "2") (pinfunction "2_2") (pintype "passive"))
      (node (ref "R12") (pin "2") (pinfunction "2_2") (pintype "passive"))
      (node (ref "R14") (pin "1") (pinfunction "1_1") (pintype "passive"))
      (node (ref "R16") (pin "2") (pinfunction "2_2") (pintype "passive"))
      (node (ref "R21") (pin "1") (pinfunction "1_1") (pintype "passive"))
      (node (ref "R28") (pin "1") (pinfunction "1_1") (pintype "passive"))
      (node (ref "R32") (pin "1") (pinfunction "1_1") (pintype "passive"))
      (node (ref "R45") (pin "2") (pinfunction "2_2") (pintype "passive"))
      (node (ref "R46") (pin "2") (pinfunction "2_2") (pintype "passive"))
      (node (ref "R6") (pin "2") (pinfunction "2_2") (pintype "passive"))
      (node (ref "S2") (pin "3") (pinfunction "S_3") (pintype "passive"))
      (node (ref "S2") (pin "4") (pinfunction "S1_4") (pintype "passive"))
      (node (ref "S3") (pin "3") (pinfunction "S_3") (pintype "passive"))
      (node (ref "S3") (pin "4") (pinfunction "S1_4") (pintype "passive"))
      (node (ref "U1") (pin "7") (pinfunction "GND_7") (pintype "passive"))
      (node (ref "U2") (pin "1") (pinfunction "GND_1") (pintype "power_in"))
      (node (ref "U2") (pin "15") (pinfunction "GND_15") (pintype "power_in"))
      (node (ref "U2") (pin "38") (pinfunction "GND_38") (pintype "power_in"))
      (node (ref "U2") (pin "39") (pinfunction "GND_39") (pintype "power_in"))
      (node (ref "U3") (pin "29") (pinfunction "GND_29") (pintype "power_in"))
      (node (ref "U3") (pin "3") (pinfunction "GND_3") (pintype "power_in"))
      (node (ref "U4") (pin "3") (pinfunction "GND_3") (pintype "bidirectional"))
      (node (ref "U5") (pin "2") (pinfunction "GND_2") (pintype "bidirectional"))
      (node (ref "U6") (pin "25") (pinfunction "VSS_25") (pintype "power_in"))
    )
    (net (code "12") (name "HOST_RMII_CLK50") (class "Default")
      (node (ref "R5") (pin "2") (pinfunction "2_2") (pintype "passive"))
      (node (ref "U6") (pin "5") (pinfunction "XTAL1/CLKLN_5") (pintype "input"))
    )
    (net (code "13") (name "HOST_RMII_CRS_DV") (class "Default")
      (node (ref "R36") (pin "2") (pinfunction "2_2") (pintype "passive"))
      (node (ref "U2") (pin "12") (pinfunction "IO27_12") (pintype "bidirectional"))
    )
    (net (code "14") (name "HOST_RMII_MDC") (class "Default")
      (node (ref "U2") (pin "37") (pinfunction "IO23_37") (pintype "bidirectional"))
      (node (ref "U6") (pin "13") (pinfunction "MDC_13") (pintype "input"))
    )
    (net (code "15") (name "HOST_RMII_MDIO") (class "Default")
      (node (ref "R33") (pin "1") (pinfunction "1_1") (pintype "passive"))
      (node (ref "U2") (pin "30") (pinfunction "IO18_30") (pintype "bidirectional"))
      (node (ref "U6") (pin "12") (pinfunction "MDIO_12") (pintype "bidirectional"))
    )
    (net (code "16") (name "HOST_RMII_RXD0") (class "Default")
      (node (ref "R34") (pin "2") (pinfunction "2_2") (pintype "passive"))
      (node (ref "U2") (pin "10") (pinfunction "IO25_10") (pintype "bidirectional"))
    )
    (net (code "17") (name "HOST_RMII_RXD1") (class "Default")
      (node (ref "R35") (pin "2") (pinfunction "2_2") (pintype "passive"))
      (node (ref "U2") (pin "11") (pinfunction "IO26_11") (pintype "bidirectional"))
    )
    (net (code "18") (name "HOST_RMII_TXD0") (class "Default")
      (node (ref "U2") (pin "31") (pinfunction "IO19_31") (pintype "bidirectional"))
      (node (ref "U6") (pin "17") (pinfunction "TXD0_17") (pintype "input"))
    )
    (net (code "19") (name "HOST_RMII_TXD1") (class "Default")
      (node (ref "U2") (pin "36") (pinfunction "IO22_36") (pintype "bidirectional"))
      (node (ref "U6") (pin "18") (pinfunction "TXD1_18") (pintype "input"))
    )
    (net (code "20") (name "HOST_RMII_TX_EN") (class "Default")
      (node (ref "U2") (pin "33") (pinfunction "IO21_33") (pintype "bidirectional"))
      (node (ref "U6") (pin "16") (pinfunction "TXEN_16") (pintype "input"))
    )
    (net (code "21") (name "IO0_BOOTMODE_SW0_UP") (class "Default")
      (node (ref "C17") (pin "1") (pinfunction "1_1") (pintype "passive"))
      (node (ref "Q1") (pin "3") (pinfunction "C_3") (pintype "passive"))
      (node (ref "R22") (pin "1") (pinfunction "1_1") (pintype "passive"))
      (node (ref "S2") (pin "1") (pinfunction "P_1") (pintype "passive"))
      (node (ref "S2") (pin "2") (pinfunction "P1_2") (pintype "passive"))
      (node (ref "U2") (pin "25") (pinfunction "IO0_25") (pintype "bidirectional"))
    )
    (net (code "22") (name "IO2_SW1_LOW") (class "Default")
      (node (ref "C13") (pin "2") (pinfunction "2_2") (pintype "passive"))
      (node (ref "R16") (pin "1") (pinfunction "1_1") (pintype "passive"))
      (node (ref "S1") (pin "1") (pinfunction "P_1") (pintype "passive"))
      (node (ref "S1") (pin "2") (pinfunction "P1_2") (pintype "passive"))
      (node (ref "U2") (pin "24") (pinfunction "IO2_24") (pintype "bidirectional"))
    )
    (net (code "23") (name "IO4_LED1G") (class "Default")
      (node (ref "R24") (pin "1") (pinfunction "1_1") (pintype "passive"))
      (node (ref "U2") (pin "26") (pinfunction "IO4_26") (pintype "bidirectional"))
    )
    (net (code "24") (name "IO5_5VIO_3A_UP") (class "Default")
      (node (ref "R9") (pin "2") (pinfunction "2_2") (pintype "passive"))
      (node (ref "U1") (pin "5") (pinfunction "A4_5") (pintype "bidirectional"))
      (node (ref "U2") (pin "29") (pinfunction "IO5_29") (pintype "bidirectional"))
    )
    (net (code "25") (name "IO12_3V3IO_0_LOW") (class "Default")
      (node (ref "J4") (pin "2") (pinfunction "2_2") (pintype "passive"))
      (node (ref "R11") (pin "1") (pinfunction "1_1") (pintype "passive"))
      (node (ref "U2") (pin "14") (pinfunction "IO12_14") (pintype "bidirectional"))
    )
    (net (code "26") (name "IO13_LED1R") (class "Default")
      (node (ref "R25") (pin "1") (pinfunction "1_1") (pintype "passive"))
      (node (ref "U2") (pin "16") (pinfunction "IO13_16") (pintype "bidirectional"))
    )
    (net (code "27") (name "IO14_LED0B") (class "Default")
      (node (ref "R17") (pin "1") (pinfunction "1_1") (pintype "passive"))
      (node (ref "U2") (pin "13") (pinfunction "IO14_13") (pintype "bidirectional"))
    )
    (net (code "28") (name "IO15_5VIO_2A_UP") (class "Default")
      (node (ref "R10") (pin "2") (pinfunction "2_2") (pintype "passive"))
      (node (ref "U1") (pin "4") (pinfunction "A3_4") (pintype "bidirectional"))
      (node (ref "U2") (pin "23") (pinfunction "IO15_23") (pintype "bidirectional"))
    )
    (net (code "29") (name "IO16_LED1B") (class "Default")
      (node (ref "R23") (pin "1") (pinfunction "1_1") (pintype "passive"))
      (node (ref "U2") (pin "27") (pinfunction "IO16_27") (pintype "bidirectional"))
    )
    (net (code "30") (name "IO32_5VIO_0A") (class "Default")
      (node (ref "U1") (pin "2") (pinfunction "A1_2") (pintype "bidirectional"))
      (node (ref "U2") (pin "8") (pinfunction "IO32_8") (pintype "bidirectional"))
    )
    (net (code "31") (name "IO33_LED0G") (class "Default")
      (node (ref "R18") (pin "1") (pinfunction "1_1") (pintype "passive"))
      (node (ref "U2") (pin "9") (pinfunction "IO33_9") (pintype "bidirectional"))
    )
    (net (code "32") (name "IO34_LED0R") (class "Default")
      (node (ref "R19") (pin "1") (pinfunction "1_1") (pintype "passive"))
      (node (ref "U2") (pin "6") (pinfunction "IO34_6") (pintype "bidirectional"))
    )
    (net (code "33") (name "IO35_5VIO_1A") (class "Default")
      (node (ref "U1") (pin "3") (pinfunction "A2_3") (pintype "bidirectional"))
      (node (ref "U2") (pin "7") (pinfunction "IO35_7") (pintype "bidirectional"))
    )
    (net (code "34") (name "IO36_VSENSE") (class "Default")
      (node (ref "C8") (pin "1") (pinfunction "1_1") (pintype "passive"))
      (node (ref "R13") (pin "1") (pinfunction "1_1") (pintype "passive"))
      (node (ref "R14") (pin "2") (pinfunction "2_2") (pintype "passive"))
      (node (ref "U2") (pin "4") (pinfunction "SENSOR_VP_4") (pintype "input"))
    )
    (net (code "35") (name "IO39_3V3IO_1_LOW") (class "Default")
      (node (ref "J4") (pin "3") (pinfunction "3_3") (pintype "passive"))
      (node (ref "R12") (pin "1") (pinfunction "1_1") (pintype "passive"))
      (node (ref "U2") (pin "5") (pinfunction "SENSOR_VN_5") (pintype "input"))
    )
    (net (code "36") (name "Net-(C16-Pad1)") (class "Default")
      (node (ref "C16") (pin "1") (pinfunction "1_1") (pintype "passive"))
      (node (ref "J7") (pin "2") (pinfunction "2_2") (pintype "passive"))
      (node (ref "L1") (pin "2") (pinfunction "2_2") (pintype "passive"))
      (node (ref "R20") (pin "2") (pinfunction "2_2") (pintype "passive"))
      (node (ref "R44") (pin "1") (pinfunction "1_1") (pintype "passive"))
    )
    (net (code "37") (name "Net-(D3-Pad2)") (class "Default")
      (node (ref "D3") (pin "2") (pinfunction "2_2") (pintype "passive"))
      (node (ref "R19") (pin "2") (pinfunction "2_2") (pintype "passive"))
    )
    (net (code "38") (name "Net-(D3-Pad3)") (class "Default")
      (node (ref "D3") (pin "3") (pinfunction "3_3") (pintype "passive"))
      (node (ref "R18") (pin "2") (pinfunction "2_2") (pintype "passive"))
    )
    (net (code "39") (name "Net-(D3-Pad4)") (class "Default")
      (node (ref "D3") (pin "4") (pinfunction "4_4") (pintype "passive"))
      (node (ref "R17") (pin "2") (pinfunction "2_2") (pintype "passive"))
    )
    (net (code "40") (name "Net-(D4-Pad2)") (class "Default")
      (node (ref "D4") (pin "2") (pinfunction "2_2") (pintype "passive"))
      (node (ref "R25") (pin "2") (pinfunction "2_2") (pintype "passive"))
    )
    (net (code "41") (name "Net-(D4-Pad3)") (class "Default")
      (node (ref "D4") (pin "3") (pinfunction "3_3") (pintype "passive"))
      (node (ref "R24") (pin "2") (pinfunction "2_2") (pintype "passive"))
    )
    (net (code "42") (name "Net-(D4-Pad4)") (class "Default")
      (node (ref "D4") (pin "4") (pinfunction "4_4") (pintype "passive"))
      (node (ref "R23") (pin "2") (pinfunction "2_2") (pintype "passive"))
    )
    (net (code "43") (name "Net-(D5-PadC)") (class "Default")
      (node (ref "D5") (pin "C") (pinfunction "C_C") (pintype "passive"))
      (node (ref "R45") (pin "1") (pinfunction "1_1") (pintype "passive"))
    )
    (net (code "44") (name "Net-(D6-PadC)") (class "Default")
      (node (ref "D6") (pin "C") (pinfunction "C_C") (pintype "passive"))
      (node (ref "R46") (pin "1") (pinfunction "1_1") (pintype "passive"))
    )
    (net (code "45") (name "Net-(J5-PadL2)") (class "Default")
      (node (ref "J5") (pin "L2") (pinfunction "L2_L2") (pintype "passive"))
      (node (ref "R40") (pin "2") (pinfunction "2_2") (pintype "passive"))
    )
    (net (code "46") (name "Net-(J5-PadL3)") (class "Default")
      (node (ref "J5") (pin "L3") (pinfunction "L3_L3") (pintype "passive"))
      (node (ref "R41") (pin "2") (pinfunction "2_2") (pintype "passive"))
    )
    (net (code "47") (name "Net-(Q1-B)") (class "Default")
      (node (ref "Q1") (pin "1") (pinfunction "B_1") (pintype "passive"))
      (node (ref "R7") (pin "2") (pinfunction "2_2") (pintype "passive"))
    )
    (net (code "48") (name "Net-(Q2-B)") (class "Default")
      (node (ref "Q2") (pin "1") (pinfunction "B_1") (pintype "passive"))
      (node (ref "R8") (pin "2") (pinfunction "2_2") (pintype "passive"))
    )
    (net (code "49") (name "Net-(U1-OE)") (class "Default")
      (node (ref "R2") (pin "2") (pinfunction "2_2") (pintype "passive"))
      (node (ref "U1") (pin "8") (pinfunction "OE_8") (pintype "input"))
    )
    (net (code "50") (name "Net-(U2-IO17)") (class "Default")
      (node (ref "R5") (pin "1") (pinfunction "1_1") (pintype "passive"))
      (node (ref "U2") (pin "28") (pinfunction "IO17_28") (pintype "bidirectional"))
    )
    (net (code "51") (name "Net-(U3-~{RST})") (class "Default")
      (node (ref "R3") (pin "2") (pinfunction "2_2") (pintype "passive"))
      (node (ref "U3") (pin "9") (pinfunction "~{RST}_9") (pintype "input"))
    )
    (net (code "52") (name "Net-(U3-~{SUSPENDB})") (class "Default")
      (node (ref "R6") (pin "1") (pinfunction "1_1") (pintype "passive"))
      (node (ref "U3") (pin "11") (pinfunction "~{SUSPENDB}_11") (pintype "output"))
    )
    (net (code "53") (name "Net-(U5-BS)") (class "Default")
      (node (ref "C15") (pin "1") (pinfunction "1_1") (pintype "passive"))
      (node (ref "U5") (pin "1") (pinfunction "BS_1") (pintype "bidirectional"))
    )
    (net (code "54") (name "Net-(U5-EN)") (class "Default")
      (node (ref "R15") (pin "2") (pinfunction "2_2") (pintype "passive"))
      (node (ref "U5") (pin "4") (pinfunction "EN_4") (pintype "bidirectional"))
    )
    (net (code "55") (name "Net-(U5-FB)") (class "Default")
      (node (ref "R20") (pin "1") (pinfunction "1_1") (pintype "passive"))
      (node (ref "R21") (pin "2") (pinfunction "2_2") (pintype "passive"))
      (node (ref "U5") (pin "3") (pinfunction "FB_3") (pintype "bidirectional"))
    )
    (net (code "56") (name "Net-(U5-LX)") (class "Default")
      (node (ref "C15") (pin "2") (pinfunction "2_2") (pintype "passive"))
      (node (ref "D2") (pin "C") (pinfunction "C_C") (pintype "passive"))
      (node (ref "L1") (pin "1") (pinfunction "1_1") (pintype "passive"))
      (node (ref "U5") (pin "6") (pinfunction "LX_6") (pintype "bidirectional"))
    )
    (net (code "57") (name "Net-(U5-VIN)") (class "Default")
      (node (ref "R15") (pin "1") (pinfunction "1_1") (pintype "passive"))
      (node (ref "R43") (pin "2") (pinfunction "2_2") (pintype "passive"))
      (node (ref "U5") (pin "5") (pinfunction "VIN_5") (pintype "bidirectional"))
    )
    (net (code "58") (name "Net-(U6-CRS_DV{slash}MODE2)") (class "Default")
      (node (ref "R31") (pin "1") (pinfunction "1_1") (pintype "passive"))
      (node (ref "R36") (pin "1") (pinfunction "1_1") (pintype "passive"))
      (node (ref "U6") (pin "11") (pinfunction "CRS_DV/MODE2_11") (pintype "bidirectional"))
    )
    (net (code "59") (name "Net-(U6-LED1{slash}REGOFF)") (class "Default")
      (node (ref "R41") (pin "1") (pinfunction "1_1") (pintype "passive"))
      (node (ref "U6") (pin "3") (pinfunction "LED1/REGOFF_3") (pintype "bidirectional"))
    )
    (net (code "60") (name "Net-(U6-LED2{slash}~{NINTSEL})") (class "Default")
      (node (ref "R40") (pin "1") (pinfunction "1_1") (pintype "passive"))
      (node (ref "U6") (pin "2") (pinfunction "LED2/~{NINTSEL}_2") (pintype "bidirectional"))
    )
    (net (code "61") (name "Net-(U6-RBIAS)") (class "Default")
      (node (ref "R28") (pin "2") (pinfunction "2_2") (pintype "passive"))
      (node (ref "U6") (pin "24") (pinfunction "RBIAS_24") (pintype "input"))
    )
    (net (code "62") (name "Net-(U6-RXD0{slash}MODE0)") (class "Default")
      (node (ref "R29") (pin "1") (pinfunction "1_1") (pintype "passive"))
      (node (ref "R34") (pin "1") (pinfunction "1_1") (pintype "passive"))
      (node (ref "U6") (pin "8") (pinfunction "RXD0/MODE0_8") (pintype "bidirectional"))
    )
    (net (code "63") (name "Net-(U6-RXD1{slash}MODE1)") (class "Default")
      (node (ref "R30") (pin "1") (pinfunction "1_1") (pintype "passive"))
      (node (ref "R35") (pin "1") (pinfunction "1_1") (pintype "passive"))
      (node (ref "U6") (pin "7") (pinfunction "RXD1/MODE1_7") (pintype "bidirectional"))
    )
    (net (code "64") (name "Net-(U6-RXER{slash}PHYADO)") (class "Default")
      (node (ref "R32") (pin "2") (pinfunction "2_2") (pintype "passive"))
      (node (ref "U6") (pin "10") (pinfunction "RXER/PHYADO_10") (pintype "bidirectional"))
    )
    (net (code "65") (name "Net-(U6-~{NRST})") (class "Default")
      (node (ref "C20") (pin "1") (pinfunction "1_1") (pintype "passive"))
      (node (ref "R26") (pin "2") (pinfunction "2_2") (pintype "passive"))
      (node (ref "R27") (pin "1") (pinfunction "1_1") (pintype "passive"))
      (node (ref "U6") (pin "15") (pinfunction "~{NRST}_15") (pintype "input"))
    )
    (net (code "66") (name "PHY_VDDCR") (class "Default")
      (node (ref "C22") (pin "1") (pinfunction "1_1") (pintype "passive"))
      (node (ref "C24") (pin "1") (pinfunction "1_1") (pintype "passive"))
      (node (ref "C25") (pin "1") (pinfunction "1_1") (pintype "passive"))
      (node (ref "U6") (pin "6") (pinfunction "VDDCR_6") (pintype "power_in"))
    )
    (net (code "67") (name "RD_N") (class "Default")
      (node (ref "J5") (pin "R8") (pinfunction "RD-_R8") (pintype "input"))
      (node (ref "R37") (pin "1") (pinfunction "1_1") (pintype "passive"))
      (node (ref "U6") (pin "22") (pinfunction "RXN_22") (pintype "bidirectional"))
    )
    (net (code "68") (name "RD_P") (class "Default")
      (node (ref "J5") (pin "R7") (pinfunction "RD+_R7") (pintype "input"))
      (node (ref "R38") (pin "1") (pinfunction "1_1") (pintype "passive"))
      (node (ref "U6") (pin "23") (pinfunction "RXP_23") (pintype "bidirectional"))
    )
    (net (code "69") (name "TD_N") (class "Default")
      (node (ref "J5") (pin "R2") (pinfunction "TD-_R2") (pintype "input"))
      (node (ref "R39") (pin "1") (pinfunction "1_1") (pintype "passive"))
      (node (ref "U6") (pin "20") (pinfunction "TXN_20") (pintype "bidirectional"))
    )
    (net (code "70") (name "TD_P") (class "Default")
      (node (ref "J5") (pin "R1") (pinfunction "TD+_R1") (pintype "input"))
      (node (ref "R42") (pin "1") (pinfunction "1_1") (pintype "passive"))
      (node (ref "U6") (pin "21") (pinfunction "TXP_21") (pintype "bidirectional"))
    )
    (net (code "71") (name "UART_DTR") (class "Default")
      (node (ref "Q1") (pin "2") (pinfunction "E_2") (pintype "passive"))
      (node (ref "R8") (pin "1") (pinfunction "1_1") (pintype "passive"))
      (node (ref "U3") (pin "28") (pinfunction "DTR_28") (pintype "output"))
    )
    (net (code "72") (name "UART_RTS") (class "Default")
      (node (ref "Q2") (pin "2") (pinfunction "E_2") (pintype "passive"))
      (node (ref "R7") (pin "1") (pinfunction "1_1") (pintype "passive"))
      (node (ref "U3") (pin "24") (pinfunction "RTS_24") (pintype "output"))
    )
    (net (code "73") (name "UART_RXD") (class "Default")
      (node (ref "U2") (pin "34") (pinfunction "RXD0_34") (pintype "bidirectional"))
      (node (ref "U3") (pin "26") (pinfunction "TXD_26") (pintype "output"))
    )
    (net (code "74") (name "UART_TXD") (class "Default")
      (node (ref "U2") (pin "35") (pinfunction "TXD0_35") (pintype "bidirectional"))
      (node (ref "U3") (pin "25") (pinfunction "RXD_25") (pintype "input"))
    )
    (net (code "75") (name "USBD_N") (class "Default")
      (node (ref "J1") (pin "3") (pinfunction "3_3") (pintype "passive"))
      (node (ref "U3") (pin "5") (pinfunction "D-_5") (pintype "bidirectional"))
    )
    (net (code "76") (name "USBD_P") (class "Default")
      (node (ref "J1") (pin "2") (pinfunction "2_2") (pintype "passive"))
      (node (ref "U3") (pin "4") (pinfunction "D+_4") (pintype "bidirectional"))
    )
    (net (code "77") (name "VBUS") (class "Default")
      (node (ref "C3") (pin "1") (pinfunction "1_1") (pintype "passive"))
      (node (ref "D1") (pin "1") (pinfunction "A_1") (pintype "passive"))
      (node (ref "J1") (pin "1") (pinfunction "1_1") (pintype "passive"))
      (node (ref "R4") (pin "1") (pinfunction "1_1") (pintype "passive"))
      (node (ref "U3") (pin "8") (pinfunction "VBUS_8") (pintype "power_in"))
    )
    (net (code "78") (name "VDDA") (class "Default")
      (node (ref "C26") (pin "1") (pinfunction "1_1") (pintype "passive"))
      (node (ref "C27") (pin "1") (pinfunction "1_1") (pintype "passive"))
      (node (ref "C28") (pin "1") (pinfunction "1_1") (pintype "passive"))
      (node (ref "C29") (pin "1") (pinfunction "1_1") (pintype "passive"))
      (node (ref "J5") (pin "L1") (pinfunction "L1_L1") (pintype "passive"))
      (node (ref "J5") (pin "R3") (pinfunction "CT_R3") (pintype "input"))
      (node (ref "L2") (pin "2") (pinfunction "2_2") (pintype "passive"))
      (node (ref "R37") (pin "2") (pinfunction "2_2") (pintype "passive"))
      (node (ref "R38") (pin "2") (pinfunction "2_2") (pintype "passive"))
      (node (ref "R39") (pin "2") (pinfunction "2_2") (pintype "passive"))
      (node (ref "R42") (pin "2") (pinfunction "2_2") (pintype "passive"))
      (node (ref "U6") (pin "1") (pinfunction "VDD2A_1") (pintype "power_in"))
      (node (ref "U6") (pin "19") (pinfunction "VDD1A_19") (pintype "power_in"))
    )
    (net (code "79") (name "VLED") (class "Default")
      (node (ref "C11") (pin "1") (pinfunction "1_1") (pintype "passive"))
      (node (ref "C12") (pin "1") (pinfunction "1_1") (pintype "passive"))
      (node (ref "C18") (pin "1") (pinfunction "1_1") (pintype "passive"))
      (node (ref "C19") (pin "1") (pinfunction "1_1") (pintype "passive"))
      (node (ref "J2") (pin "3") (pinfunction "1_3") (pintype "passive"))
      (node (ref "J3") (pin "3") (pinfunction "1_3") (pintype "passive"))
      (node (ref "R13") (pin "2") (pinfunction "2_2") (pintype "passive"))
      (node (ref "R4") (pin "2") (pinfunction "2_2") (pintype "passive"))
      (node (ref "R43") (pin "1") (pinfunction "1_1") (pintype "passive"))
      (node (ref "U4") (pin "2") (pinfunction "VIN_2") (pintype "bidirectional"))
    )
    (net (code "80") (name "unconnected-(J1-Pad4)") (class "Default")
      (node (ref "J1") (pin "4") (pinfunction "4_4") (pintype "passive"))
    )
    (net (code "81") (name "unconnected-(J5-PadR4)") (class "Default")
      (node (ref "J5") (pin "R4") (pinfunction "R4_R4") (pintype "input"))
    )
    (net (code "82") (name "unconnected-(J5-PadR5)") (class "Default")
      (node (ref "J5") (pin "R5") (pinfunction "R5_R5") (pintype "input"))
    )
    (net (code "83") (name "unconnected-(J5-PadR6)") (class "Default")
      (node (ref "J5") (pin "R6") (pinfunction "R6_R6") (pintype "input"))
    )
    (net (code "84") (name "unconnected-(U1-NC-Pad6)") (class "Default")
      (node (ref "U1") (pin "6") (pinfunction "NC_6") (pintype "no_connect"))
    )
    (net (code "85") (name "unconnected-(U1-NC_2-Pad9)") (class "Default")
      (node (ref "U1") (pin "9") (pinfunction "NC_2_9") (pintype "no_connect"))
    )
    (net (code "86") (name "unconnected-(U2-SCL{slash}CLK-Pad20)") (class "Default")
      (node (ref "U2") (pin "20") (pinfunction "SCL/CLK_20") (pintype "bidirectional"))
    )
    (net (code "87") (name "unconnected-(U2-SCS{slash}CMD-Pad19)") (class "Default")
      (node (ref "U2") (pin "19") (pinfunction "SCS/CMD_19") (pintype "bidirectional"))
    )
    (net (code "88") (name "unconnected-(U2-SDI{slash}SD1-Pad22)") (class "Default")
      (node (ref "U2") (pin "22") (pinfunction "SDI/SD1_22") (pintype "bidirectional"))
    )
    (net (code "89") (name "unconnected-(U2-SDO{slash}SD0-Pad21)") (class "Default")
      (node (ref "U2") (pin "21") (pinfunction "SDO/SD0_21") (pintype "bidirectional"))
    )
    (net (code "90") (name "unconnected-(U2-SHD{slash}SD2-Pad17)") (class "Default")
      (node (ref "U2") (pin "17") (pinfunction "SHD/SD2_17") (pintype "bidirectional"))
    )
    (net (code "91") (name "unconnected-(U2-SWP{slash}SD3-Pad18)") (class "Default")
      (node (ref "U2") (pin "18") (pinfunction "SWP/SD3_18") (pintype "bidirectional"))
    )
    (net (code "92") (name "unconnected-(U3-CHR0-Pad15)") (class "Default")
      (node (ref "U3") (pin "15") (pinfunction "CHR0_15") (pintype "output"))
    )
    (net (code "93") (name "unconnected-(U3-CHR1-Pad14)") (class "Default")
      (node (ref "U3") (pin "14") (pinfunction "CHR1_14") (pintype "output"))
    )
    (net (code "94") (name "unconnected-(U3-CHREN-Pad13)") (class "Default")
      (node (ref "U3") (pin "13") (pinfunction "CHREN_13") (pintype "output"))
    )
    (net (code "95") (name "unconnected-(U3-CTS-Pad23)") (class "Default")
      (node (ref "U3") (pin "23") (pinfunction "CTS_23") (pintype "input"))
    )
    (net (code "96") (name "unconnected-(U3-DCD-Pad1)") (class "Default")
      (node (ref "U3") (pin "1") (pinfunction "DCD_1") (pintype "input"))
    )
    (net (code "97") (name "unconnected-(U3-DSR-Pad27)") (class "Default")
      (node (ref "U3") (pin "27") (pinfunction "DSR_27") (pintype "input"))
    )
    (net (code "98") (name "unconnected-(U3-GPIO.0{slash}TXT-Pad19)") (class "Default")
      (node (ref "U3") (pin "19") (pinfunction "GPIO.0/TXT_19") (pintype "bidirectional"))
    )
    (net (code "99") (name "unconnected-(U3-GPIO.1{slash}RXT-Pad18)") (class "Default")
      (node (ref "U3") (pin "18") (pinfunction "GPIO.1/RXT_18") (pintype "bidirectional"))
    )
    (net (code "100") (name "unconnected-(U3-GPIO.2{slash}RS485-Pad17)") (class "Default")
      (node (ref "U3") (pin "17") (pinfunction "GPIO.2/RS485_17") (pintype "bidirectional"))
    )
    (net (code "101") (name "unconnected-(U3-GPIO.3{slash}WAKEUP-Pad16)") (class "Default")
      (node (ref "U3") (pin "16") (pinfunction "GPIO.3/WAKEUP_16") (pintype "bidirectional"))
    )
    (net (code "102") (name "unconnected-(U3-GPIO.4-Pad22)") (class "Default")
      (node (ref "U3") (pin "22") (pinfunction "GPIO.4_22") (pintype "bidirectional"))
    )
    (net (code "103") (name "unconnected-(U3-GPIO.5-Pad21)") (class "Default")
      (node (ref "U3") (pin "21") (pinfunction "GPIO.5_21") (pintype "bidirectional"))
    )
    (net (code "104") (name "unconnected-(U3-GPIO.6-Pad20)") (class "Default")
      (node (ref "U3") (pin "20") (pinfunction "GPIO.6_20") (pintype "bidirectional"))
    )
    (net (code "105") (name "unconnected-(U3-RI{slash}CLK-Pad2)") (class "Default")
      (node (ref "U3") (pin "2") (pinfunction "RI/CLK_2") (pintype "bidirectional"))
    )
    (net (code "106") (name "unconnected-(U3-SUSPEND-Pad12)") (class "Default")
      (node (ref "U3") (pin "12") (pinfunction "SUSPEND_12") (pintype "output"))
    )
    (net (code "107") (name "unconnected-(U6-XTAL2-Pad4)") (class "Default")
      (node (ref "U6") (pin "4") (pinfunction "XTAL2_4") (pintype "output"))
    )
    (net (code "108") (name "unconnected-(U6-~{NINT}{slash}REFCLKO-Pad14)") (class "Default")
      (node (ref "U6") (pin "14") (pinfunction "~{NINT}/REFCLKO_14") (pintype "output"))
    )
    (net (code "109") (name "~{RESET}") (class "Default")
      (node (ref "C2") (pin "1") (pinfunction "1_1") (pintype "passive"))
      (node (ref "Q2") (pin "3") (pinfunction "C_3") (pintype "passive"))
      (node (ref "R1") (pin "1") (pinfunction "1_1") (pintype "passive"))
      (node (ref "R26") (pin "1") (pinfunction "1_1") (pintype "passive"))
      (node (ref "S3") (pin "1") (pinfunction "P_1") (pintype "passive"))
      (node (ref "S3") (pin "2") (pinfunction "P1_2") (pintype "passive"))
      (node (ref "U2") (pin "3") (pinfunction "EN_3") (pintype "input"))
    )
  )
)
